# base_station.net
KiCad netlist of a schematic drawn in Altium Designer
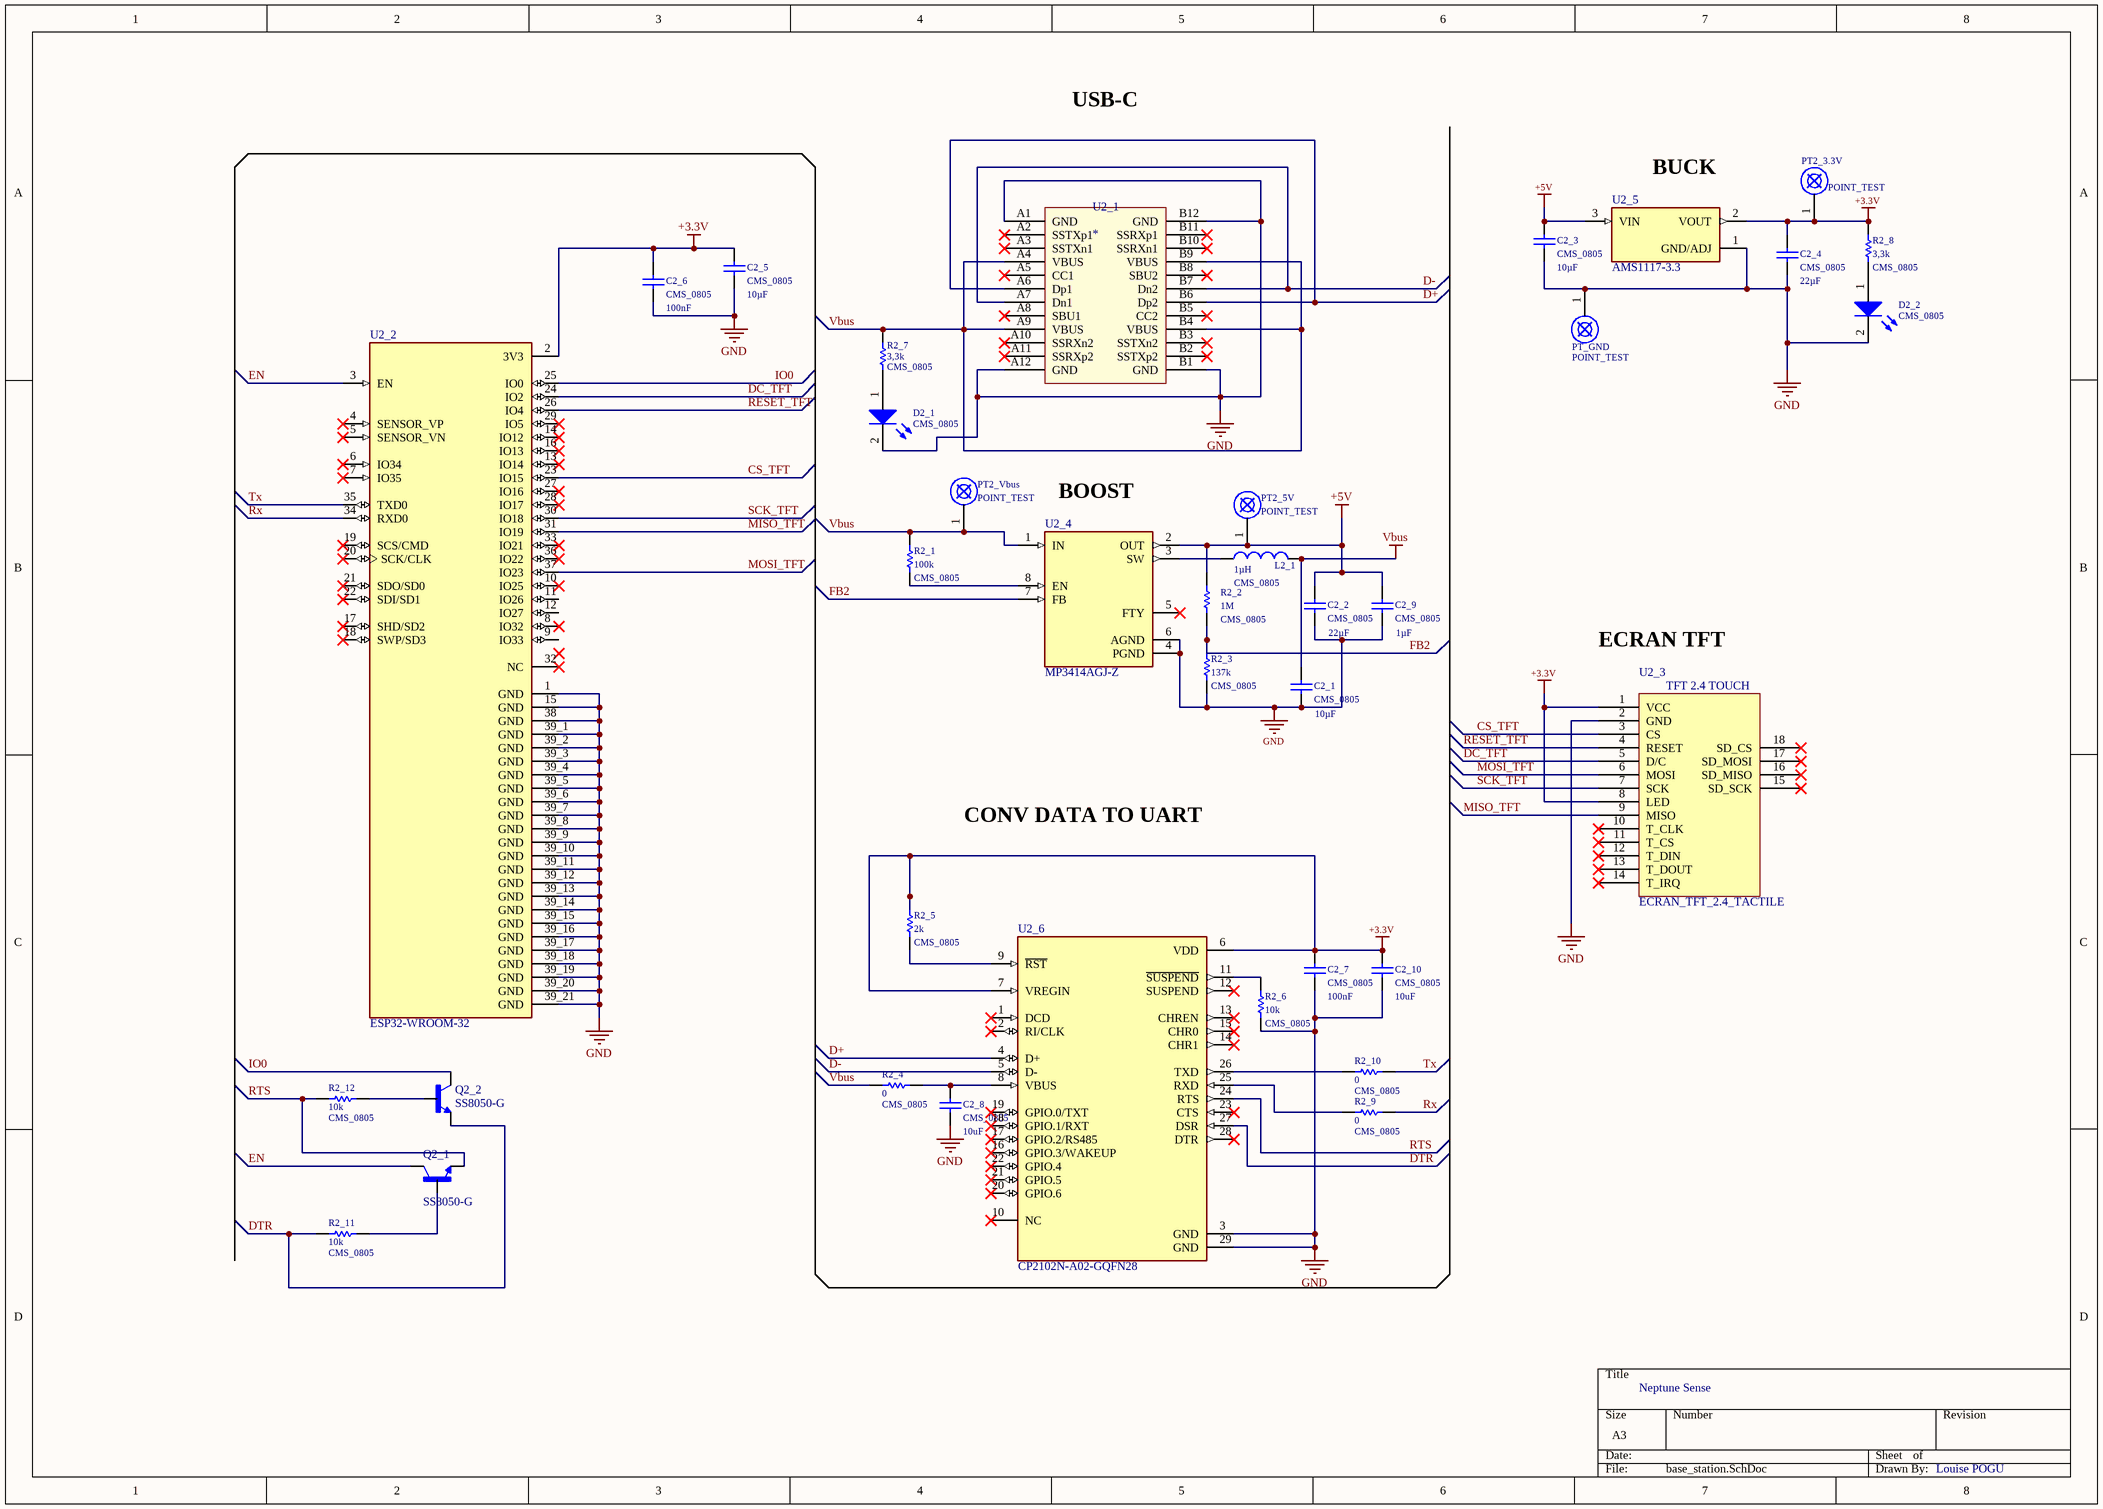
[diagram p0: base_station.SchDoc]

(export (version "E")
  (design (tool "Eeschema 10.0.6"))
  (components
    (comp (ref "C2_1")
      (value "10µF")
      (footprint "CONDENSATEUR_CMS_0805")
      (description "CONDENSATEUR CMS CERAMIQUE 0805")
      (fields (field (name "TYPE") "CMS_0805") (field (name "Comment") "CMS_0805"))
      (libsource (lib "composants passifs") (part "CONDENSATEUR_CMS_CER_0805"))
    )
    (comp (ref "C2_2")
      (value "22µF")
      (footprint "CONDENSATEUR_CMS_0805")
      (description "CONDENSATEUR CMS CERAMIQUE 0805")
      (fields (field (name "TYPE") "CMS_0805") (field (name "Comment") "CMS_0805"))
      (libsource (lib "composants passifs") (part "CONDENSATEUR_CMS_CER_0805"))
    )
    (comp (ref "C2_3")
      (value "10µF")
      (footprint "CONDENSATEUR_CMS_0805")
      (description "CONDENSATEUR CMS CERAMIQUE 0805")
      (fields (field (name "TYPE") "CMS_0805") (field (name "Comment") "CMS_0805"))
      (libsource (lib "composants passifs") (part "CONDENSATEUR_CMS_CER_0805"))
    )
    (comp (ref "C2_4")
      (value "22µF")
      (footprint "CONDENSATEUR_CMS_0805")
      (description "CONDENSATEUR CMS CERAMIQUE 0805")
      (fields (field (name "TYPE") "CMS_0805") (field (name "Comment") "CMS_0805"))
      (libsource (lib "composants passifs") (part "CONDENSATEUR_CMS_CER_0805"))
    )
    (comp (ref "C2_5")
      (value "10µF")
      (footprint "CONDENSATEUR_CMS_0805")
      (description "CONDENSATEUR CMS CERAMIQUE 0805")
      (fields (field (name "TYPE") "CMS_0805") (field (name "Comment") "CMS_0805"))
      (libsource (lib "composants passifs") (part "CONDENSATEUR_CMS_CER_0805"))
    )
    (comp (ref "C2_6")
      (value "100nF")
      (footprint "CONDENSATEUR_CMS_0805")
      (description "CONDENSATEUR CMS CERAMIQUE 0805")
      (fields (field (name "TYPE") "CMS_0805") (field (name "Comment") "CMS_0805"))
      (libsource (lib "composants passifs") (part "CONDENSATEUR_CMS_CER_0805"))
    )
    (comp (ref "C2_7")
      (value "100nF")
      (footprint "CONDENSATEUR_CMS_0805")
      (description "CONDENSATEUR CMS CERAMIQUE 0805")
      (fields (field (name "TYPE") "CMS_0805") (field (name "Comment") "CMS_0805"))
      (libsource (lib "composants passifs") (part "CONDENSATEUR_CMS_CER_0805"))
    )
    (comp (ref "C2_8")
      (value "10uF")
      (footprint "CONDENSATEUR_CMS_0805")
      (description "CONDENSATEUR CMS CERAMIQUE 0805")
      (fields (field (name "TYPE") "CMS_0805") (field (name "Comment") "CMS_0805"))
      (libsource (lib "composants passifs") (part "CONDENSATEUR_CMS_CER_0805"))
    )
    (comp (ref "C2_9")
      (value "1µF")
      (footprint "CONDENSATEUR_CMS_0805")
      (description "CONDENSATEUR CMS CERAMIQUE 0805")
      (fields (field (name "TYPE") "CMS_0805") (field (name "Comment") "CMS_0805"))
      (libsource (lib "composants passifs") (part "CONDENSATEUR_CMS_CER_0805"))
    )
    (comp (ref "C2_10")
      (value "10uF")
      (footprint "CONDENSATEUR_CMS_0805")
      (description "CONDENSATEUR CMS CERAMIQUE 0805")
      (fields (field (name "TYPE") "CMS_0805") (field (name "Comment") "CMS_0805"))
      (libsource (lib "composants passifs") (part "CONDENSATEUR_CMS_CER_0805"))
    )
    (comp (ref "D2_1")
      (value "LED_CMS_0805")
      (footprint "LED_CMS_0805")
      (description "LED CMS 0805")
      (fields (field (name "TYPE") "CMS_0805"))
      (libsource (lib "affichage") (part "LED_CMS_0805"))
    )
    (comp (ref "D2_2")
      (value "LED_CMS_0805")
      (footprint "LED_CMS_0805")
      (description "LED CMS 0805")
      (fields (field (name "TYPE") "CMS_0805"))
      (libsource (lib "affichage") (part "LED_CMS_0805"))
    )
    (comp (ref "L2_1")
      (value "1µH")
      (footprint "INDUCTANCE_CMS_0805")
      (description "INDUCTANCE CMS 0805")
      (fields (field (name "TYPE") "CMS_0805") (field (name "Comment") "INDUCTANCE_CMS_0805"))
      (libsource (lib "composants passifs") (part "INDUCTANCE_CMS_0805"))
    )
    (comp (ref "PT2_3.3V")
      (value "POINT_TEST")
      (footprint "POINT_TEST")
      (description "POINT TEST")
      (fields (field (name "SOURCE") "connecteurs.SchLib"))
      (libsource (lib "ESEO (Ecole Supérieure d'Electronique de l'Ouest)") (part "POINT_TEST"))
    )
    (comp (ref "PT2_5V")
      (value "POINT_TEST")
      (footprint "POINT_TEST")
      (description "POINT TEST")
      (fields (field (name "SOURCE") "connecteurs.SchLib"))
      (libsource (lib "ESEO (Ecole Supérieure d'Electronique de l'Ouest)") (part "POINT_TEST"))
    )
    (comp (ref "PT2_Vbus")
      (value "POINT_TEST")
      (footprint "POINT_TEST")
      (description "POINT TEST")
      (fields (field (name "SOURCE") "connecteurs.SchLib"))
      (libsource (lib "ESEO (Ecole Supérieure d'Electronique de l'Ouest)") (part "POINT_TEST"))
    )
    (comp (ref "PT_GND")
      (value "POINT_TEST")
      (footprint "POINT_TEST")
      (description "POINT TEST")
      (fields (field (name "SOURCE") "connecteurs.SchLib"))
      (libsource (lib "ESEO (Ecole Supérieure d'Electronique de l'Ouest)") (part "POINT_TEST"))
    )
    (comp (ref "Q2_1")
      (value "SS8050-G")
      (footprint "TRANS_SS8050-G")
      (description "Bipolar (BJT) Transistor NPN 25 V 1.5 A 100MHz 300 mW Surface Mount SOT-23-3")
      (fields (field (name "MP") "SS8050G") (field (name "MF") "Comchip"))
      (libsource (lib "") (part "SS8050-G_1"))
    )
    (comp (ref "Q2_2")
      (value "SS8050-G")
      (footprint "TRANS_SS8050-G")
      (description "Bipolar (BJT) Transistor NPN 25 V 1.5 A 100MHz 300 mW Surface Mount SOT-23-3")
      (fields (field (name "MP") "SS8050G") (field (name "MF") "Comchip"))
      (libsource (lib "ESEO (Ecole Supérieure d'Electronique de l'Ouest)") (part "SS8050-G"))
    )
    (comp (ref "R2_1")
      (value "100k")
      (footprint "RESISTANCE_CMS_0805")
      (description "RESISTANCE CMS 0805")
      (fields (field (name "TYPE") "CMS_0805") (field (name "Comment") "RESISTANCE_CMS_0805"))
      (libsource (lib "composants passifs") (part "RESISTANCE_CMS_0805"))
    )
    (comp (ref "R2_2")
      (value "1M")
      (footprint "RESISTANCE_CMS_0805")
      (description "RESISTANCE CMS 0805")
      (fields (field (name "TYPE") "CMS_0805") (field (name "Comment") "RESISTANCE_CMS_0805"))
      (libsource (lib "composants passifs") (part "RESISTANCE_CMS_0805"))
    )
    (comp (ref "R2_3")
      (value "137k")
      (footprint "RESISTANCE_CMS_0805")
      (description "RESISTANCE CMS 0805")
      (fields (field (name "TYPE") "CMS_0805") (field (name "Comment") "RESISTANCE_CMS_0805"))
      (libsource (lib "composants passifs") (part "RESISTANCE_CMS_0805"))
    )
    (comp (ref "R2_4")
      (value "0")
      (footprint "RESISTANCE_CMS_0805")
      (description "RESISTANCE CMS 0805")
      (fields (field (name "TYPE") "CMS_0805") (field (name "Comment") "RESISTANCE_CMS_0805"))
      (libsource (lib "composants passifs") (part "RESISTANCE_CMS_0805"))
    )
    (comp (ref "R2_5")
      (value "2k")
      (footprint "RESISTANCE_CMS_0805")
      (description "RESISTANCE CMS 0805")
      (fields (field (name "TYPE") "CMS_0805") (field (name "Comment") "RESISTANCE_CMS_0805"))
      (libsource (lib "composants passifs") (part "RESISTANCE_CMS_0805"))
    )
    (comp (ref "R2_6")
      (value "10k")
      (footprint "RESISTANCE_CMS_0805")
      (description "RESISTANCE CMS 0805")
      (fields (field (name "TYPE") "CMS_0805") (field (name "Comment") "RESISTANCE_CMS_0805"))
      (libsource (lib "composants passifs") (part "RESISTANCE_CMS_0805"))
    )
    (comp (ref "R2_7")
      (value "3,3k")
      (footprint "RESISTANCE_CMS_0805")
      (description "RESISTANCE CMS 0805")
      (fields (field (name "TYPE") "CMS_0805") (field (name "Comment") "RESISTANCE_CMS_0805"))
      (libsource (lib "composants passifs") (part "RESISTANCE_CMS_0805"))
    )
    (comp (ref "R2_8")
      (value "3,3k")
      (footprint "RESISTANCE_CMS_0805")
      (description "RESISTANCE CMS 0805")
      (fields (field (name "TYPE") "CMS_0805") (field (name "Comment") "RESISTANCE_CMS_0805"))
      (libsource (lib "composants passifs") (part "RESISTANCE_CMS_0805"))
    )
    (comp (ref "R2_9")
      (value "0")
      (footprint "RESISTANCE_CMS_0805")
      (description "RESISTANCE CMS 0805")
      (fields (field (name "TYPE") "CMS_0805") (field (name "Comment") "RESISTANCE_CMS_0805"))
      (libsource (lib "composants passifs") (part "RESISTANCE_CMS_0805"))
    )
    (comp (ref "R2_10")
      (value "0")
      (footprint "RESISTANCE_CMS_0805")
      (description "RESISTANCE CMS 0805")
      (fields (field (name "TYPE") "CMS_0805") (field (name "Comment") "RESISTANCE_CMS_0805"))
      (libsource (lib "composants passifs") (part "RESISTANCE_CMS_0805"))
    )
    (comp (ref "R2_11")
      (value "10k")
      (footprint "RESISTANCE_CMS_0805")
      (description "RESISTANCE CMS 0805")
      (fields (field (name "TYPE") "CMS_0805") (field (name "Comment") "RESISTANCE_CMS_0805"))
      (libsource (lib "composants passifs") (part "RESISTANCE_CMS_0805"))
    )
    (comp (ref "R2_12")
      (value "10k")
      (footprint "RESISTANCE_CMS_0805")
      (description "RESISTANCE CMS 0805")
      (fields (field (name "TYPE") "CMS_0805") (field (name "Comment") "RESISTANCE_CMS_0805"))
      (libsource (lib "composants passifs") (part "RESISTANCE_CMS_0805"))
    )
    (comp (ref "U2_1") (value "*") (footprint "USB") (libsource (lib "*") (part "USB")))
    (comp (ref "U2_2")
      (value "ESP32-WROOM-32")
      (footprint "MODULE_ESP32-WROOM-32")
      (fields (field (name "MF") "Espressif Systems"))
      (libsource (lib "ESEO (Ecole Supérieure d'Electronique de l'Ouest)") (part "ESP32-WROOM-32"))
    )
    (comp (ref "U2_3")
      (value "ECRAN_TFT_2.4_TACTILE")
      (footprint "ECRAN_TFT_2.4_TACTILE")
      (libsource (lib "affichage") (part "ECRAN_TFT_2.4_TACTILE"))
    )
    (comp (ref "U2_4")
      (value "MP3414AGJ-Z")
      (footprint "SOT65P280X100-8N")
      (description "Boost Switching Regulator IC Positive Adjustable 2V 1 Output 3A SOT-23-8")
      (fields (field (name "MF") "Monolithic Power"))
      (libsource (lib "ESEO (Ecole Supérieure d'Electronique de l'Ouest)") (part "MP3414AGJ-Z"))
    )
    (comp (ref "U2_5")
      (value "AMS1117-3.3")
      (footprint "SOT229P700X180-4N")
      (description "LDO Voltage Regulators 800MA LDO LINEAR REG")
      (fields (field (name "MF") "ams AG"))
      (libsource (lib "ESEO (Ecole Supérieure d'Electronique de l'Ouest)") (part "AMS1117-3.3"))
    )
    (comp (ref "U2_6")
      (value "CP2102N-A02-GQFN28")
      (footprint "QFN50P500X500X80-29N")
      (description "USB Bridge, USB to UART USB 2.0 UART Interface 28-QFN (5x5)")
      (fields (field (name "MF") "Silicon Labs"))
      (libsource (lib "ESEO (Ecole Supérieure d'Electronique de l'Ouest)") (part "CP2102N-A02-GQFN28"))
    )
  )
  (nets
    (net (code "1") (name "+3.3V") (class "Default")
      (node (ref "C2_10") (pin "2") (pinfunction "2_2") (pintype "passive"))
      (node (ref "C2_4") (pin "2") (pinfunction "2_2") (pintype "passive"))
      (node (ref "C2_5") (pin "2") (pinfunction "2_2") (pintype "passive"))
      (node (ref "C2_6") (pin "2") (pinfunction "2_2") (pintype "passive"))
      (node (ref "C2_7") (pin "2") (pinfunction "2_2") (pintype "passive"))
      (node (ref "PT2_3.3V") (pin "1") (pinfunction "3_1") (pintype "passive"))
      (node (ref "R2_5") (pin "2") (pinfunction "2_2") (pintype "passive"))
      (node (ref "R2_8") (pin "2") (pinfunction "2_2") (pintype "passive"))
      (node (ref "U2_2") (pin "2") (pinfunction "3V3_2") (pintype "power_in"))
      (node (ref "U2_3") (pin "1") (pinfunction "VCC_1") (pintype "passive"))
      (node (ref "U2_3") (pin "8") (pinfunction "LED_8") (pintype "passive"))
      (node (ref "U2_5") (pin "2") (pinfunction "VOUT_2") (pintype "output"))
      (node (ref "U2_6") (pin "6") (pinfunction "VDD_6") (pintype "power_in"))
      (node (ref "U2_6") (pin "7") (pinfunction "VREGIN_7") (pintype "input"))
    )
    (net (code "2") (name "+5V") (class "Default")
      (node (ref "C2_2") (pin "2") (pinfunction "2_2") (pintype "passive"))
      (node (ref "C2_3") (pin "1") (pinfunction "1_1") (pintype "passive"))
      (node (ref "C2_9") (pin "2") (pinfunction "2_2") (pintype "passive"))
      (node (ref "PT2_5V") (pin "1") (pinfunction "3_1") (pintype "passive"))
      (node (ref "R2_2") (pin "2") (pinfunction "2_2") (pintype "passive"))
      (node (ref "U2_4") (pin "2") (pinfunction "OUT_2") (pintype "output"))
      (node (ref "U2_5") (pin "3") (pinfunction "VIN_3") (pintype "input"))
    )
    (net (code "3") (name "/CS_TFT") (class "Default")
      (node (ref "U2_2") (pin "23") (pinfunction "IO15_23") (pintype "bidirectional"))
      (node (ref "U2_3") (pin "3") (pinfunction "CS_3") (pintype "passive"))
    )
    (net (code "4") (name "/D+") (class "Default")
      (node (ref "U2_1") (pin "A6") (pinfunction "Dp1_A6") (pintype "passive"))
      (node (ref "U2_1") (pin "B6") (pinfunction "Dp2_B6") (pintype "passive"))
      (node (ref "U2_6") (pin "4") (pinfunction "D+_4") (pintype "bidirectional"))
    )
    (net (code "5") (name "/D-") (class "Default")
      (node (ref "U2_1") (pin "A7") (pinfunction "Dn1_A7") (pintype "passive"))
      (node (ref "U2_1") (pin "B7") (pinfunction "Dn2_B7") (pintype "passive"))
      (node (ref "U2_6") (pin "5") (pinfunction "D-_5") (pintype "bidirectional"))
    )
    (net (code "6") (name "/DC_TFT") (class "Default")
      (node (ref "U2_2") (pin "24") (pinfunction "IO2_24") (pintype "bidirectional"))
      (node (ref "U2_3") (pin "5") (pinfunction "D/C_5") (pintype "passive"))
    )
    (net (code "7") (name "/DTR") (class "Default")
      (node (ref "Q2_2") (pin "2") (pinfunction "E_2") (pintype "passive"))
      (node (ref "R2_11") (pin "2") (pinfunction "2_2") (pintype "passive"))
      (node (ref "U2_6") (pin "27") (pinfunction "DSR_27") (pintype "input"))
    )
    (net (code "8") (name "/EN") (class "Default")
      (node (ref "Q2_1") (pin "3") (pinfunction "C_3") (pintype "passive"))
      (node (ref "U2_2") (pin "3") (pinfunction "EN_3") (pintype "input"))
    )
    (net (code "9") (name "/FB2") (class "Default")
      (node (ref "R2_2") (pin "1") (pinfunction "1_1") (pintype "passive"))
      (node (ref "R2_3") (pin "2") (pinfunction "2_2") (pintype "passive"))
      (node (ref "U2_4") (pin "7") (pinfunction "FB_7") (pintype "input"))
    )
    (net (code "10") (name "/IO0") (class "Default")
      (node (ref "Q2_2") (pin "3") (pinfunction "C_3") (pintype "passive"))
      (node (ref "U2_2") (pin "25") (pinfunction "IO0_25") (pintype "bidirectional"))
    )
    (net (code "11") (name "/MISO_TFT") (class "Default")
      (node (ref "U2_2") (pin "31") (pinfunction "IO19_31") (pintype "bidirectional"))
      (node (ref "U2_3") (pin "9") (pinfunction "MISO_9") (pintype "passive"))
    )
    (net (code "12") (name "/MOSI_TFT") (class "Default")
      (node (ref "U2_2") (pin "37") (pinfunction "IO23_37") (pintype "bidirectional"))
      (node (ref "U2_3") (pin "6") (pinfunction "MOSI_6") (pintype "passive"))
    )
    (net (code "13") (name "/RESET_TFT") (class "Default")
      (node (ref "U2_2") (pin "26") (pinfunction "IO4_26") (pintype "bidirectional"))
      (node (ref "U2_3") (pin "4") (pinfunction "RESET_4") (pintype "passive"))
    )
    (net (code "14") (name "/RTS") (class "Default")
      (node (ref "Q2_1") (pin "2") (pinfunction "E_2") (pintype "passive"))
      (node (ref "R2_12") (pin "2") (pinfunction "2_2") (pintype "passive"))
      (node (ref "U2_6") (pin "24") (pinfunction "RTS_24") (pintype "output"))
    )
    (net (code "15") (name "/Rx") (class "Default")
      (node (ref "R2_9") (pin "1") (pinfunction "1_1") (pintype "passive"))
      (node (ref "U2_2") (pin "34") (pinfunction "RXD0_34") (pintype "bidirectional"))
    )
    (net (code "16") (name "/SCK_TFT") (class "Default")
      (node (ref "U2_2") (pin "30") (pinfunction "IO18_30") (pintype "bidirectional"))
      (node (ref "U2_3") (pin "7") (pinfunction "SCK_7") (pintype "passive"))
    )
    (net (code "17") (name "/Tx") (class "Default")
      (node (ref "R2_10") (pin "1") (pinfunction "1_1") (pintype "passive"))
      (node (ref "U2_2") (pin "35") (pinfunction "TXD0_35") (pintype "bidirectional"))
    )
    (net (code "18") (name "GND") (class "Default")
      (node (ref "C2_1") (pin "1") (pinfunction "1_1") (pintype "passive"))
      (node (ref "C2_10") (pin "1") (pinfunction "1_1") (pintype "passive"))
      (node (ref "C2_2") (pin "1") (pinfunction "1_1") (pintype "passive"))
      (node (ref "C2_3") (pin "2") (pinfunction "2_2") (pintype "passive"))
      (node (ref "C2_4") (pin "1") (pinfunction "1_1") (pintype "passive"))
      (node (ref "C2_5") (pin "1") (pinfunction "1_1") (pintype "passive"))
      (node (ref "C2_6") (pin "1") (pinfunction "1_1") (pintype "passive"))
      (node (ref "C2_7") (pin "1") (pinfunction "1_1") (pintype "passive"))
      (node (ref "C2_8") (pin "1") (pinfunction "1_1") (pintype "passive"))
      (node (ref "C2_9") (pin "1") (pinfunction "1_1") (pintype "passive"))
      (node (ref "D2_1") (pin "2") (pinfunction "2_2") (pintype "passive"))
      (node (ref "D2_2") (pin "2") (pinfunction "2_2") (pintype "passive"))
      (node (ref "PT_GND") (pin "1") (pinfunction "3_1") (pintype "passive"))
      (node (ref "R2_3") (pin "1") (pinfunction "1_1") (pintype "passive"))
      (node (ref "R2_6") (pin "1") (pinfunction "1_1") (pintype "passive"))
      (node (ref "U2_1") (pin "A1") (pinfunction "GND_A1") (pintype "passive"))
      (node (ref "U2_1") (pin "A12") (pinfunction "GND_A12") (pintype "passive"))
      (node (ref "U2_1") (pin "B1") (pinfunction "GND_B1") (pintype "passive"))
      (node (ref "U2_1") (pin "B12") (pinfunction "GND_B12") (pintype "passive"))
      (node (ref "U2_2") (pin "1") (pinfunction "GND_1") (pintype "power_in"))
      (node (ref "U2_2") (pin "15") (pinfunction "GND_15") (pintype "power_in"))
      (node (ref "U2_2") (pin "38") (pinfunction "GND_38") (pintype "power_in"))
      (node (ref "U2_2") (pin "39_1") (pinfunction "GND_39_1") (pintype "power_in"))
      (node (ref "U2_2") (pin "39_10") (pinfunction "GND_39_10") (pintype "power_in"))
      (node (ref "U2_2") (pin "39_11") (pinfunction "GND_39_11") (pintype "power_in"))
      (node (ref "U2_2") (pin "39_12") (pinfunction "GND_39_12") (pintype "power_in"))
      (node (ref "U2_2") (pin "39_13") (pinfunction "GND_39_13") (pintype "power_in"))
      (node (ref "U2_2") (pin "39_14") (pinfunction "GND_39_14") (pintype "power_in"))
      (node (ref "U2_2") (pin "39_15") (pinfunction "GND_39_15") (pintype "power_in"))
      (node (ref "U2_2") (pin "39_16") (pinfunction "GND_39_16") (pintype "power_in"))
      (node (ref "U2_2") (pin "39_17") (pinfunction "GND_39_17") (pintype "power_in"))
      (node (ref "U2_2") (pin "39_18") (pinfunction "GND_39_18") (pintype "power_in"))
      (node (ref "U2_2") (pin "39_19") (pinfunction "GND_39_19") (pintype "power_in"))
      (node (ref "U2_2") (pin "39_2") (pinfunction "GND_39_2") (pintype "power_in"))
      (node (ref "U2_2") (pin "39_20") (pinfunction "GND_39_20") (pintype "power_in"))
      (node (ref "U2_2") (pin "39_21") (pinfunction "GND_39_21") (pintype "power_in"))
      (node (ref "U2_2") (pin "39_3") (pinfunction "GND_39_3") (pintype "power_in"))
      (node (ref "U2_2") (pin "39_4") (pinfunction "GND_39_4") (pintype "power_in"))
      (node (ref "U2_2") (pin "39_5") (pinfunction "GND_39_5") (pintype "power_in"))
      (node (ref "U2_2") (pin "39_6") (pinfunction "GND_39_6") (pintype "power_in"))
      (node (ref "U2_2") (pin "39_7") (pinfunction "GND_39_7") (pintype "power_in"))
      (node (ref "U2_2") (pin "39_8") (pinfunction "GND_39_8") (pintype "power_in"))
      (node (ref "U2_2") (pin "39_9") (pinfunction "GND_39_9") (pintype "power_in"))
      (node (ref "U2_3") (pin "2") (pinfunction "GND_2") (pintype "passive"))
      (node (ref "U2_4") (pin "4") (pinfunction "PGND_4") (pintype "power_in"))
      (node (ref "U2_4") (pin "6") (pinfunction "AGND_6") (pintype "power_in"))
      (node (ref "U2_5") (pin "1") (pinfunction "GND/ADJ_1") (pintype "power_in"))
      (node (ref "U2_6") (pin "29") (pinfunction "GND_29") (pintype "power_in"))
      (node (ref "U2_6") (pin "3") (pinfunction "GND_3") (pintype "power_in"))
    )
    (net (code "19") (name "Net-(D2_1-Pad1)") (class "Default")
      (node (ref "D2_1") (pin "1") (pinfunction "1_1") (pintype "passive"))
      (node (ref "R2_7") (pin "2") (pinfunction "2_2") (pintype "passive"))
    )
    (net (code "20") (name "Net-(D2_2-Pad1)") (class "Default")
      (node (ref "D2_2") (pin "1") (pinfunction "1_1") (pintype "passive"))
      (node (ref "R2_8") (pin "1") (pinfunction "1_1") (pintype "passive"))
    )
    (net (code "21") (name "Net-(Q2_1-B)") (class "Default")
      (node (ref "Q2_1") (pin "1") (pinfunction "B_1") (pintype "passive"))
      (node (ref "R2_11") (pin "1") (pinfunction "1_1") (pintype "passive"))
    )
    (net (code "22") (name "Net-(Q2_2-B)") (class "Default")
      (node (ref "Q2_2") (pin "1") (pinfunction "B_1") (pintype "passive"))
      (node (ref "R2_12") (pin "1") (pinfunction "1_1") (pintype "passive"))
    )
    (net (code "23") (name "Net-(U2_4-EN)") (class "Default")
      (node (ref "R2_1") (pin "1") (pinfunction "1_1") (pintype "passive"))
      (node (ref "U2_4") (pin "8") (pinfunction "EN_8") (pintype "input"))
    )
    (net (code "24") (name "Net-(U2_4-SW)") (class "Default")
      (node (ref "L2_1") (pin "1") (pinfunction "1_1") (pintype "passive"))
      (node (ref "U2_4") (pin "3") (pinfunction "SW_3") (pintype "output"))
    )
    (net (code "25") (name "Net-(U2_6-RXD)") (class "Default")
      (node (ref "R2_9") (pin "2") (pinfunction "2_2") (pintype "passive"))
      (node (ref "U2_6") (pin "25") (pinfunction "RXD_25") (pintype "input"))
    )
    (net (code "26") (name "Net-(U2_6-TXD)") (class "Default")
      (node (ref "R2_10") (pin "2") (pinfunction "2_2") (pintype "passive"))
      (node (ref "U2_6") (pin "26") (pinfunction "TXD_26") (pintype "output"))
    )
    (net (code "27") (name "Net-(U2_6-VBUS)") (class "Default")
      (node (ref "C2_8") (pin "2") (pinfunction "2_2") (pintype "passive"))
      (node (ref "R2_4") (pin "1") (pinfunction "1_1") (pintype "passive"))
      (node (ref "U2_6") (pin "8") (pinfunction "VBUS_8") (pintype "input"))
    )
    (net (code "28") (name "Net-(U2_6-~{RST})") (class "Default")
      (node (ref "R2_5") (pin "1") (pinfunction "1_1") (pintype "passive"))
      (node (ref "U2_6") (pin "9") (pinfunction "~{RST}_9") (pintype "input"))
    )
    (net (code "29") (name "Net-(U2_6-~{SUSPEND})") (class "Default")
      (node (ref "R2_6") (pin "2") (pinfunction "2_2") (pintype "passive"))
      (node (ref "U2_6") (pin "11") (pinfunction "~{SUSPEND}_11") (pintype "output"))
    )
    (net (code "30") (name "Vbus") (class "Default")
      (node (ref "C2_1") (pin "2") (pinfunction "2_2") (pintype "passive"))
      (node (ref "L2_1") (pin "2") (pinfunction "2_2") (pintype "passive"))
      (node (ref "PT2_Vbus") (pin "1") (pinfunction "3_1") (pintype "passive"))
      (node (ref "R2_1") (pin "2") (pinfunction "2_2") (pintype "passive"))
      (node (ref "R2_4") (pin "2") (pinfunction "2_2") (pintype "passive"))
      (node (ref "R2_7") (pin "1") (pinfunction "1_1") (pintype "passive"))
      (node (ref "U2_1") (pin "A4") (pinfunction "VBUS_A4") (pintype "passive"))
      (node (ref "U2_1") (pin "A9") (pinfunction "VBUS_A9") (pintype "passive"))
      (node (ref "U2_1") (pin "B4") (pinfunction "VBUS_B4") (pintype "passive"))
      (node (ref "U2_1") (pin "B9") (pinfunction "VBUS_B9") (pintype "passive"))
      (node (ref "U2_4") (pin "1") (pinfunction "IN_1") (pintype "input"))
    )
    (net (code "31") (name "unconnected-(U2_1-CC1-PadA5)") (class "Default")
      (node (ref "U2_1") (pin "A5") (pinfunction "CC1_A5") (pintype "passive+no_connect"))
    )
    (net (code "32") (name "unconnected-(U2_1-CC2-PadB5)") (class "Default")
      (node (ref "U2_1") (pin "B5") (pinfunction "CC2_B5") (pintype "passive+no_connect"))
    )
    (net (code "33") (name "unconnected-(U2_1-SBU1-PadA8)") (class "Default")
      (node (ref "U2_1") (pin "A8") (pinfunction "SBU1_A8") (pintype "passive+no_connect"))
    )
    (net (code "34") (name "unconnected-(U2_1-SBU2-PadB8)") (class "Default")
      (node (ref "U2_1") (pin "B8") (pinfunction "SBU2_B8") (pintype "passive+no_connect"))
    )
    (net (code "35") (name "unconnected-(U2_1-SSRXn1-PadB10)") (class "Default")
      (node (ref "U2_1") (pin "B10") (pinfunction "SSRXn1_B10") (pintype "passive+no_connect"))
    )
    (net (code "36") (name "unconnected-(U2_1-SSRXn2-PadA10)") (class "Default")
      (node (ref "U2_1") (pin "A10") (pinfunction "SSRXn2_A10") (pintype "passive+no_connect"))
    )
    (net (code "37") (name "unconnected-(U2_1-SSRXp1-PadB11)") (class "Default")
      (node (ref "U2_1") (pin "B11") (pinfunction "SSRXp1_B11") (pintype "passive+no_connect"))
    )
    (net (code "38") (name "unconnected-(U2_1-SSRXp2-PadA11)") (class "Default")
      (node (ref "U2_1") (pin "A11") (pinfunction "SSRXp2_A11") (pintype "passive+no_connect"))
    )
    (net (code "39") (name "unconnected-(U2_1-SSTXn1-PadA3)") (class "Default")
      (node (ref "U2_1") (pin "A3") (pinfunction "SSTXn1_A3") (pintype "passive+no_connect"))
    )
    (net (code "40") (name "unconnected-(U2_1-SSTXn2-PadB3)") (class "Default")
      (node (ref "U2_1") (pin "B3") (pinfunction "SSTXn2_B3") (pintype "passive+no_connect"))
    )
    (net (code "41") (name "unconnected-(U2_1-SSTXp1-PadA2)") (class "Default")
      (node (ref "U2_1") (pin "A2") (pinfunction "SSTXp1_A2") (pintype "passive+no_connect"))
    )
    (net (code "42") (name "unconnected-(U2_1-SSTXp2-PadB2)") (class "Default")
      (node (ref "U2_1") (pin "B2") (pinfunction "SSTXp2_B2") (pintype "passive+no_connect"))
    )
    (net (code "43") (name "unconnected-(U2_2-IO5-Pad29)") (class "Default")
      (node (ref "U2_2") (pin "29") (pinfunction "IO5_29") (pintype "bidirectional+no_connect"))
    )
    (net (code "44") (name "unconnected-(U2_2-IO12-Pad14)") (class "Default")
      (node (ref "U2_2") (pin "14") (pinfunction "IO12_14") (pintype "bidirectional+no_connect"))
    )
    (net (code "45") (name "unconnected-(U2_2-IO13-Pad16)") (class "Default")
      (node (ref "U2_2") (pin "16") (pinfunction "IO13_16") (pintype "bidirectional+no_connect"))
    )
    (net (code "46") (name "unconnected-(U2_2-IO14-Pad13)") (class "Default")
      (node (ref "U2_2") (pin "13") (pinfunction "IO14_13") (pintype "bidirectional+no_connect"))
    )
    (net (code "47") (name "unconnected-(U2_2-IO16-Pad27)") (class "Default")
      (node (ref "U2_2") (pin "27") (pinfunction "IO16_27") (pintype "bidirectional+no_connect"))
    )
    (net (code "48") (name "unconnected-(U2_2-IO17-Pad28)") (class "Default")
      (node (ref "U2_2") (pin "28") (pinfunction "IO17_28") (pintype "bidirectional+no_connect"))
    )
    (net (code "49") (name "unconnected-(U2_2-IO21-Pad33)") (class "Default")
      (node (ref "U2_2") (pin "33") (pinfunction "IO21_33") (pintype "bidirectional+no_connect"))
    )
    (net (code "50") (name "unconnected-(U2_2-IO22-Pad36)") (class "Default")
      (node (ref "U2_2") (pin "36") (pinfunction "IO22_36") (pintype "bidirectional+no_connect"))
    )
    (net (code "51") (name "unconnected-(U2_2-IO25-Pad10)") (class "Default")
      (node (ref "U2_2") (pin "10") (pinfunction "IO25_10") (pintype "bidirectional+no_connect"))
    )
    (net (code "52") (name "unconnected-(U2_2-IO26-Pad11)") (class "Default")
      (node (ref "U2_2") (pin "11") (pinfunction "IO26_11") (pintype "bidirectional"))
    )
    (net (code "53") (name "unconnected-(U2_2-IO27-Pad12)") (class "Default")
      (node (ref "U2_2") (pin "12") (pinfunction "IO27_12") (pintype "bidirectional"))
    )
    (net (code "54") (name "unconnected-(U2_2-IO32-Pad8)") (class "Default")
      (node (ref "U2_2") (pin "8") (pinfunction "IO32_8") (pintype "bidirectional+no_connect"))
    )
    (net (code "55") (name "unconnected-(U2_2-IO33-Pad9)") (class "Default")
      (node (ref "U2_2") (pin "9") (pinfunction "IO33_9") (pintype "bidirectional"))
    )
    (net (code "56") (name "unconnected-(U2_2-IO34-Pad6)") (class "Default")
      (node (ref "U2_2") (pin "6") (pinfunction "IO34_6") (pintype "input+no_connect"))
    )
    (net (code "57") (name "unconnected-(U2_2-IO35-Pad7)") (class "Default")
      (node (ref "U2_2") (pin "7") (pinfunction "IO35_7") (pintype "input+no_connect"))
    )
    (net (code "58") (name "unconnected-(U2_2-NC-Pad32)") (class "Default")
      (node (ref "U2_2") (pin "32") (pinfunction "NC_32") (pintype "passive+no_connect"))
    )
    (net (code "59") (name "unconnected-(U2_2-SCK{slash}CLK-Pad20)") (class "Default")
      (node (ref "U2_2") (pin "20") (pinfunction "SCK/CLK_20") (pintype "bidirectional+no_connect"))
    )
    (net (code "60") (name "unconnected-(U2_2-SCS{slash}CMD-Pad19)") (class "Default")
      (node (ref "U2_2") (pin "19") (pinfunction "SCS/CMD_19") (pintype "bidirectional+no_connect"))
    )
    (net (code "61") (name "unconnected-(U2_2-SDI{slash}SD1-Pad22)") (class "Default")
      (node (ref "U2_2") (pin "22") (pinfunction "SDI/SD1_22") (pintype "bidirectional+no_connect"))
    )
    (net (code "62") (name "unconnected-(U2_2-SDO{slash}SD0-Pad21)") (class "Default")
      (node (ref "U2_2") (pin "21") (pinfunction "SDO/SD0_21") (pintype "bidirectional+no_connect"))
    )
    (net (code "63") (name "unconnected-(U2_2-SENSOR_VN-Pad5)") (class "Default")
      (node (ref "U2_2") (pin "5") (pinfunction "SENSOR_VN_5") (pintype "input+no_connect"))
    )
    (net (code "64") (name "unconnected-(U2_2-SENSOR_VP-Pad4)") (class "Default")
      (node (ref "U2_2") (pin "4") (pinfunction "SENSOR_VP_4") (pintype "input+no_connect"))
    )
    (net (code "65") (name "unconnected-(U2_2-SHD{slash}SD2-Pad17)") (class "Default")
      (node (ref "U2_2") (pin "17") (pinfunction "SHD/SD2_17") (pintype "bidirectional+no_connect"))
    )
    (net (code "66") (name "unconnected-(U2_2-SWP{slash}SD3-Pad18)") (class "Default")
      (node (ref "U2_2") (pin "18") (pinfunction "SWP/SD3_18") (pintype "bidirectional+no_connect"))
    )
    (net (code "67") (name "unconnected-(U2_3-SD_CS-Pad18)") (class "Default")
      (node (ref "U2_3") (pin "18") (pinfunction "SD_CS_18") (pintype "passive+no_connect"))
    )
    (net (code "68") (name "unconnected-(U2_3-SD_MISO-Pad16)") (class "Default")
      (node (ref "U2_3") (pin "16") (pinfunction "SD_MISO_16") (pintype "passive+no_connect"))
    )
    (net (code "69") (name "unconnected-(U2_3-SD_MOSI-Pad17)") (class "Default")
      (node (ref "U2_3") (pin "17") (pinfunction "SD_MOSI_17") (pintype "passive+no_connect"))
    )
    (net (code "70") (name "unconnected-(U2_3-SD_SCK-Pad15)") (class "Default")
      (node (ref "U2_3") (pin "15") (pinfunction "SD_SCK_15") (pintype "passive+no_connect"))
    )
    (net (code "71") (name "unconnected-(U2_3-T_CLK-Pad10)") (class "Default")
      (node (ref "U2_3") (pin "10") (pinfunction "T_CLK_10") (pintype "passive+no_connect"))
    )
    (net (code "72") (name "unconnected-(U2_3-T_CS-Pad11)") (class "Default")
      (node (ref "U2_3") (pin "11") (pinfunction "T_CS_11") (pintype "passive+no_connect"))
    )
    (net (code "73") (name "unconnected-(U2_3-T_DIN-Pad12)") (class "Default")
      (node (ref "U2_3") (pin "12") (pinfunction "T_DIN_12") (pintype "passive+no_connect"))
    )
    (net (code "74") (name "unconnected-(U2_3-T_DOUT-Pad13)") (class "Default")
      (node (ref "U2_3") (pin "13") (pinfunction "T_DOUT_13") (pintype "passive+no_connect"))
    )
    (net (code "75") (name "unconnected-(U2_3-T_IRQ-Pad14)") (class "Default")
      (node (ref "U2_3") (pin "14") (pinfunction "T_IRQ_14") (pintype "passive+no_connect"))
    )
    (net (code "76") (name "unconnected-(U2_4-FTY-Pad5)") (class "Default")
      (node (ref "U2_4") (pin "5") (pinfunction "FTY_5") (pintype "passive+no_connect"))
    )
    (net (code "77") (name "unconnected-(U2_6-CHR0-Pad15)") (class "Default")
      (node (ref "U2_6") (pin "15") (pinfunction "CHR0_15") (pintype "output+no_connect"))
    )
    (net (code "78") (name "unconnected-(U2_6-CHR1-Pad14)") (class "Default")
      (node (ref "U2_6") (pin "14") (pinfunction "CHR1_14") (pintype "output+no_connect"))
    )
    (net (code "79") (name "unconnected-(U2_6-CHREN-Pad13)") (class "Default")
      (node (ref "U2_6") (pin "13") (pinfunction "CHREN_13") (pintype "output+no_connect"))
    )
    (net (code "80") (name "unconnected-(U2_6-CTS-Pad23)") (class "Default")
      (node (ref "U2_6") (pin "23") (pinfunction "CTS_23") (pintype "input+no_connect"))
    )
    (net (code "81") (name "unconnected-(U2_6-DCD-Pad1)") (class "Default")
      (node (ref "U2_6") (pin "1") (pinfunction "DCD_1") (pintype "input+no_connect"))
    )
    (net (code "82") (name "unconnected-(U2_6-DTR-Pad28)") (class "Default")
      (node (ref "U2_6") (pin "28") (pinfunction "DTR_28") (pintype "output+no_connect"))
    )
    (net (code "83") (name "unconnected-(U2_6-GPIO.0{slash}TXT-Pad19)") (class "Default")
      (node (ref "U2_6") (pin "19") (pinfunction "GPIO.0/TXT_19") (pintype "bidirectional+no_connect"))
    )
    (net (code "84") (name "unconnected-(U2_6-GPIO.1{slash}RXT-Pad18)") (class "Default")
      (node (ref "U2_6") (pin "18") (pinfunction "GPIO.1/RXT_18") (pintype "bidirectional+no_connect"))
    )
    (net (code "85") (name "unconnected-(U2_6-GPIO.2{slash}RS485-Pad17)") (class "Default")
      (node (ref "U2_6") (pin "17") (pinfunction "GPIO.2/RS485_17") (pintype "bidirectional+no_connect"))
    )
    (net (code "86") (name "unconnected-(U2_6-GPIO.3{slash}WAKEUP-Pad16)") (class "Default")
      (node (ref "U2_6") (pin "16") (pinfunction "GPIO.3/WAKEUP_16") (pintype "bidirectional+no_connect"))
    )
    (net (code "87") (name "unconnected-(U2_6-GPIO.4-Pad22)") (class "Default")
      (node (ref "U2_6") (pin "22") (pinfunction "GPIO.4_22") (pintype "bidirectional+no_connect"))
    )
    (net (code "88") (name "unconnected-(U2_6-GPIO.5-Pad21)") (class "Default")
      (node (ref "U2_6") (pin "21") (pinfunction "GPIO.5_21") (pintype "bidirectional+no_connect"))
    )
    (net (code "89") (name "unconnected-(U2_6-GPIO.6-Pad20)") (class "Default")
      (node (ref "U2_6") (pin "20") (pinfunction "GPIO.6_20") (pintype "bidirectional+no_connect"))
    )
    (net (code "90") (name "unconnected-(U2_6-NC-Pad10)") (class "Default")
      (node (ref "U2_6") (pin "10") (pinfunction "NC_10") (pintype "passive+no_connect"))
    )
    (net (code "91") (name "unconnected-(U2_6-RI{slash}CLK-Pad2)") (class "Default")
      (node (ref "U2_6") (pin "2") (pinfunction "RI/CLK_2") (pintype "bidirectional+no_connect"))
    )
    (net (code "92") (name "unconnected-(U2_6-SUSPEND-Pad12)") (class "Default")
      (node (ref "U2_6") (pin "12") (pinfunction "SUSPEND_12") (pintype "output+no_connect"))
    )
  )
)
